# double-wired-3-face-board.net
KiCad netlist of a schematic drawn in EAGLE
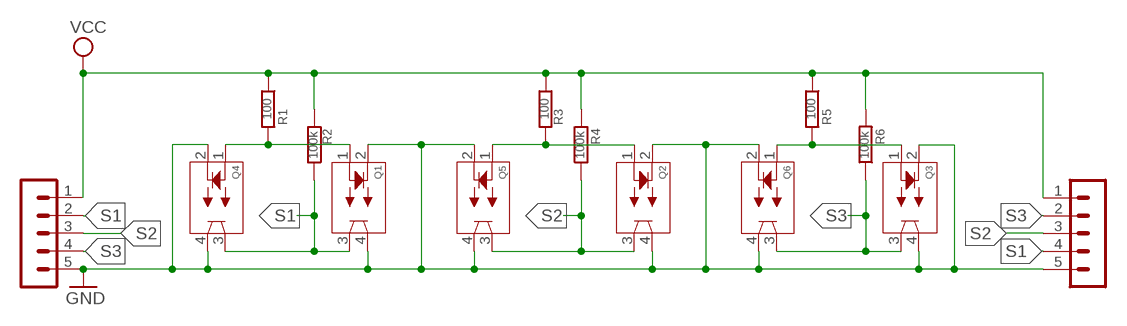
[diagram p0: schematic, sheet 1]

(export (version "E")
  (design (tool "Eeschema 10.0.6"))
  (components
    (comp (ref "Q1")
      (value "QRE1113")
      (footprint "eagle-import:DIP4_100AQ_ONS")
      (fields (field (name "COPYRIGHT") "Copyright (C) 2024 Ultra Librarian. All rights reserved."))
      (libsource (lib "eagle-import") (part "QRE1113"))
    )
    (comp (ref "Q2")
      (value "QRE1113")
      (footprint "eagle-import:DIP4_100AQ_ONS")
      (fields (field (name "COPYRIGHT") "Copyright (C) 2024 Ultra Librarian. All rights reserved."))
      (libsource (lib "eagle-import") (part "QRE1113"))
    )
    (comp (ref "Q3")
      (value "QRE1113")
      (footprint "eagle-import:DIP4_100AQ_ONS")
      (fields (field (name "COPYRIGHT") "Copyright (C) 2024 Ultra Librarian. All rights reserved."))
      (libsource (lib "eagle-import") (part "QRE1113"))
    )
    (comp (ref "Q4")
      (value "QRE1113")
      (footprint "eagle-import:DIP4_100AQ_ONS")
      (fields (field (name "COPYRIGHT") "Copyright (C) 2024 Ultra Librarian. All rights reserved."))
      (libsource (lib "eagle-import") (part "QRE1113"))
    )
    (comp (ref "Q5")
      (value "QRE1113")
      (footprint "eagle-import:DIP4_100AQ_ONS")
      (fields (field (name "COPYRIGHT") "Copyright (C) 2024 Ultra Librarian. All rights reserved."))
      (libsource (lib "eagle-import") (part "QRE1113"))
    )
    (comp (ref "Q6")
      (value "QRE1113")
      (footprint "eagle-import:DIP4_100AQ_ONS")
      (fields (field (name "COPYRIGHT") "Copyright (C) 2024 Ultra Librarian. All rights reserved."))
      (libsource (lib "eagle-import") (part "QRE1113"))
    )
    (comp (ref "R1")
      (value "100")
      (footprint "eagle-import:0207_10")
      (libsource (lib "eagle-import") (part "R-EU_0207/10"))
    )
    (comp (ref "R2")
      (value "100k")
      (footprint "eagle-import:0207_10")
      (libsource (lib "eagle-import") (part "R-EU_0207/10"))
    )
    (comp (ref "R3")
      (value "100")
      (footprint "eagle-import:0207_10")
      (libsource (lib "eagle-import") (part "R-EU_0207/10"))
    )
    (comp (ref "R4")
      (value "100k")
      (footprint "eagle-import:0207_10")
      (libsource (lib "eagle-import") (part "R-EU_0207/10"))
    )
    (comp (ref "R5")
      (value "100")
      (footprint "eagle-import:0207_10")
      (libsource (lib "eagle-import") (part "R-EU_0207/10"))
    )
    (comp (ref "R6")
      (value "100k")
      (footprint "eagle-import:0207_10")
      (libsource (lib "eagle-import") (part "R-EU_0207/10"))
    )
    (comp (ref "SV1")
      (value "on")
      (footprint "eagle-import:MA05-1")
      (libsource (lib "eagle-import") (part "MA05-1"))
    )
    (comp (ref "SV2")
      (value "on")
      (footprint "eagle-import:MA05-1")
      (libsource (lib "eagle-import") (part "MA05-1"))
    )
  )
  (nets
    (net (code "1") (name "GND") (class "Default")
      (node (ref "Q1") (pin "2") (pinfunction "2_2") (pintype "passive"))
      (node (ref "Q1") (pin "4") (pinfunction "4_4") (pintype "passive"))
      (node (ref "Q2") (pin "2") (pinfunction "2_2") (pintype "passive"))
      (node (ref "Q2") (pin "4") (pinfunction "4_4") (pintype "passive"))
      (node (ref "Q3") (pin "2") (pinfunction "2_2") (pintype "passive"))
      (node (ref "Q3") (pin "4") (pinfunction "4_4") (pintype "passive"))
      (node (ref "Q4") (pin "2") (pinfunction "2_2") (pintype "passive"))
      (node (ref "Q4") (pin "4") (pinfunction "4_4") (pintype "passive"))
      (node (ref "Q5") (pin "2") (pinfunction "2_2") (pintype "passive"))
      (node (ref "Q5") (pin "4") (pinfunction "4_4") (pintype "passive"))
      (node (ref "Q6") (pin "2") (pinfunction "2_2") (pintype "passive"))
      (node (ref "Q6") (pin "4") (pinfunction "4_4") (pintype "passive"))
      (node (ref "SV1") (pin "5") (pinfunction "5_5") (pintype "passive"))
      (node (ref "SV2") (pin "5") (pinfunction "5_5") (pintype "passive"))
    )
    (net (code "2") (name "Net-(Q1-Pad1)") (class "Default")
      (node (ref "Q1") (pin "1") (pinfunction "1_1") (pintype "passive"))
      (node (ref "Q4") (pin "1") (pinfunction "1_1") (pintype "passive"))
      (node (ref "R1") (pin "2") (pinfunction "2_2") (pintype "passive"))
    )
    (net (code "3") (name "Net-(Q2-Pad1)") (class "Default")
      (node (ref "Q2") (pin "1") (pinfunction "1_1") (pintype "passive"))
      (node (ref "Q5") (pin "1") (pinfunction "1_1") (pintype "passive"))
      (node (ref "R3") (pin "2") (pinfunction "2_2") (pintype "passive"))
    )
    (net (code "4") (name "Net-(Q3-Pad1)") (class "Default")
      (node (ref "Q3") (pin "1") (pinfunction "1_1") (pintype "passive"))
      (node (ref "Q6") (pin "1") (pinfunction "1_1") (pintype "passive"))
      (node (ref "R5") (pin "2") (pinfunction "2_2") (pintype "passive"))
    )
    (net (code "5") (name "S1") (class "Default")
      (node (ref "Q1") (pin "3") (pinfunction "3_3") (pintype "passive"))
      (node (ref "Q4") (pin "3") (pinfunction "3_3") (pintype "passive"))
      (node (ref "R2") (pin "1") (pinfunction "1_1") (pintype "passive"))
      (node (ref "SV1") (pin "4") (pinfunction "4_4") (pintype "passive"))
      (node (ref "SV2") (pin "2") (pinfunction "2_2") (pintype "passive"))
    )
    (net (code "6") (name "S2") (class "Default")
      (node (ref "Q2") (pin "3") (pinfunction "3_3") (pintype "passive"))
      (node (ref "Q5") (pin "3") (pinfunction "3_3") (pintype "passive"))
      (node (ref "R4") (pin "1") (pinfunction "1_1") (pintype "passive"))
      (node (ref "SV1") (pin "3") (pinfunction "3_3") (pintype "passive"))
      (node (ref "SV2") (pin "3") (pinfunction "3_3") (pintype "passive"))
    )
    (net (code "7") (name "S3") (class "Default")
      (node (ref "Q3") (pin "3") (pinfunction "3_3") (pintype "passive"))
      (node (ref "Q6") (pin "3") (pinfunction "3_3") (pintype "passive"))
      (node (ref "R6") (pin "1") (pinfunction "1_1") (pintype "passive"))
      (node (ref "SV1") (pin "2") (pinfunction "2_2") (pintype "passive"))
      (node (ref "SV2") (pin "4") (pinfunction "4_4") (pintype "passive"))
    )
    (net (code "8") (name "VCC") (class "Default")
      (node (ref "R1") (pin "1") (pinfunction "1_1") (pintype "passive"))
      (node (ref "R2") (pin "2") (pinfunction "2_2") (pintype "passive"))
      (node (ref "R3") (pin "1") (pinfunction "1_1") (pintype "passive"))
      (node (ref "R4") (pin "2") (pinfunction "2_2") (pintype "passive"))
      (node (ref "R5") (pin "1") (pinfunction "1_1") (pintype "passive"))
      (node (ref "R6") (pin "2") (pinfunction "2_2") (pintype "passive"))
      (node (ref "SV1") (pin "1") (pinfunction "1_1") (pintype "passive"))
      (node (ref "SV2") (pin "1") (pinfunction "1_1") (pintype "passive"))
    )
  )
)
